# RaceDAQ_ANALOG.net
KiCad netlist of a schematic drawn in Altium Designer
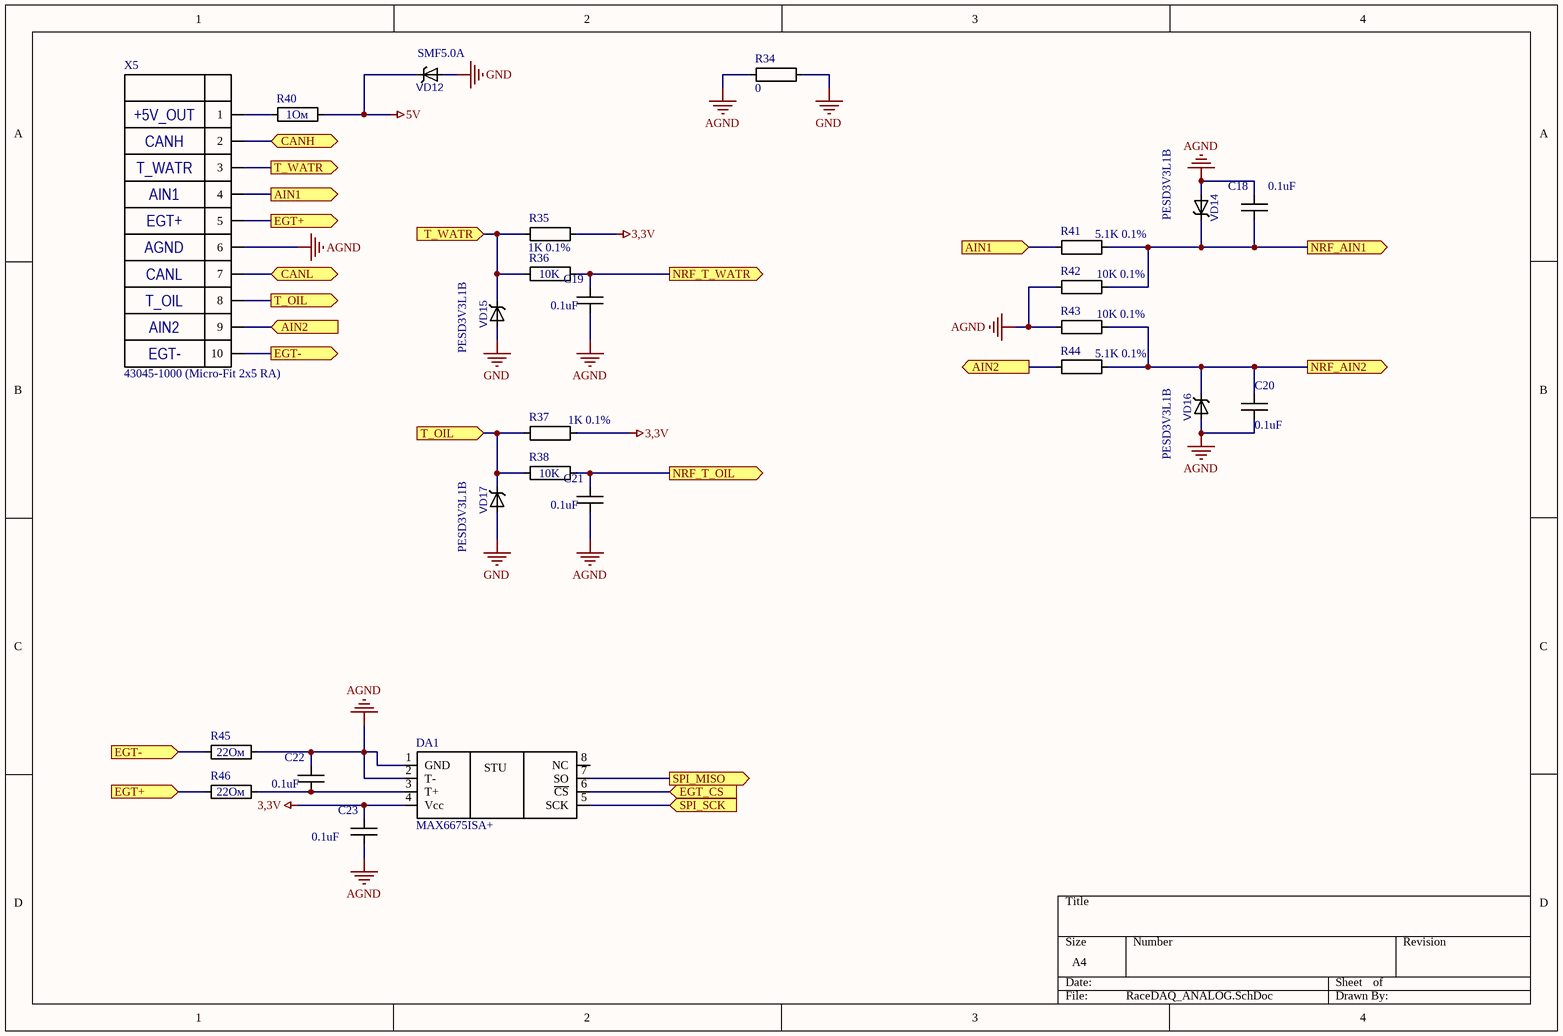
[diagram p0: RaceDAQ_ANALOG.SchDoc]

(export (version "E")
  (design (tool "Eeschema 10.0.6"))
  (components
    (comp (ref "C18")
      (value "0.1uF")
      (footprint "CAPC1608X90L25N")
      (fields (field (name "VOLTAGE") "50V") (field (name "PARTNUMBER") "CL10B104KB8NNNC"))
      (libsource (lib "tlib") (part "CAP"))
    )
    (comp (ref "C19")
      (value "0.1uF")
      (footprint "CAPC1608X90L25N")
      (fields (field (name "VOLTAGE") "50V") (field (name "PARTNUMBER") "CL10B104KB8NNNC"))
      (libsource (lib "tlib") (part "CAP"))
    )
    (comp (ref "C20")
      (value "0.1uF")
      (footprint "CAPC1608X90L25N")
      (fields (field (name "VOLTAGE") "50V") (field (name "PARTNUMBER") "CL10B104KB8NNNC"))
      (libsource (lib "tlib") (part "CAP"))
    )
    (comp (ref "C21")
      (value "0.1uF")
      (footprint "CAPC1608X90L25N")
      (fields (field (name "VOLTAGE") "50V") (field (name "PARTNUMBER") "CL10B104KB8NNNC"))
      (libsource (lib "tlib") (part "CAP"))
    )
    (comp (ref "C22")
      (value "0.1uF")
      (footprint "CAPC1608X90L25N")
      (fields (field (name "VOLTAGE") "50V") (field (name "PARTNUMBER") "CL10B104KB8NNNC"))
      (libsource (lib "tlib") (part "CAP"))
    )
    (comp (ref "C23")
      (value "0.1uF")
      (footprint "CAPC1608X90L25N")
      (fields (field (name "VOLTAGE") "50V") (field (name "PARTNUMBER") "CL10B104KB8NNNC"))
      (libsource (lib "tlib") (part "CAP"))
    )
    (comp (ref "DA1")
      (value "MAX6675ISA+")
      (footprint "SOIC127P600X175-8L87N")
      (libsource (lib "tlib") (part "MAX6675ISA+"))
    )
    (comp (ref "R34") (value "0") (footprint "RESC2012X60L35N") (libsource (lib "tlib") (part "RES")))
    (comp (ref "R35")
      (value "1K 0.1%")
      (footprint "RESC1608X55L25N")
      (fields (field (name "PARTNUMBER") "RT0603BRD071KL"))
      (libsource (lib "tlib") (part "RES"))
    )
    (comp (ref "R36") (value "10K") (footprint "RESC2012X60L35N") (libsource (lib "tlib") (part "RES")))
    (comp (ref "R37")
      (value "1K 0.1%")
      (footprint "RESC1608X55L25N")
      (fields (field (name "PARTNUMBER") "RT0603BRD071KL"))
      (libsource (lib "tlib") (part "RES"))
    )
    (comp (ref "R38") (value "10K") (footprint "RESC2012X60L35N") (libsource (lib "tlib") (part "RES")))
    (comp (ref "R40")
      (value "1Ом")
      (footprint "RESC1608X55L25N")
      (fields (field (name "PARTNUMBER") "RT0603BRD071KL"))
      (libsource (lib "tlib") (part "RES"))
    )
    (comp (ref "R41")
      (value "5.1K 0.1%")
      (footprint "RESC1608X55L25N")
      (fields (field (name "PARTNUMBER") "RT0603BRD075K1L"))
      (libsource (lib "tlib") (part "RES"))
    )
    (comp (ref "R42")
      (value "10K 0.1%")
      (footprint "RESC1608X55L25N")
      (fields (field (name "PARTNUMBER") "RT0603BRD0710KL"))
      (libsource (lib "tlib") (part "RES"))
    )
    (comp (ref "R43")
      (value "10K 0.1%")
      (footprint "RESC1608X55L25N")
      (fields (field (name "PARTNUMBER") "RT0603BRD0710KL"))
      (libsource (lib "tlib") (part "RES"))
    )
    (comp (ref "R44")
      (value "5.1K 0.1%")
      (footprint "RESC1608X55L25N")
      (fields (field (name "PARTNUMBER") "RT0603BRD075K1L"))
      (libsource (lib "tlib") (part "RES"))
    )
    (comp (ref "R45") (value "22Ом") (footprint "RESC1608X55L25N") (libsource (lib "tlib") (part "RES")))
    (comp (ref "R46") (value "22Ом") (footprint "RESC1608X55L25N") (libsource (lib "tlib") (part "RES")))
    (comp (ref "VD12") (value "SMF5.0A") (footprint "SODFL3617X110") (libsource (lib "tlib") (part "TVS_AC")))
    (comp (ref "VD14")
      (value "PESD3V3L1B")
      (footprint "SODFL1608X65N")
      (libsource (lib "tlib") (part "TVS_AC"))
    )
    (comp (ref "VD15")
      (value "PESD3V3L1B")
      (footprint "SODFL1608X65N")
      (libsource (lib "tlib") (part "TVS_AC"))
    )
    (comp (ref "VD16")
      (value "PESD3V3L1B")
      (footprint "SODFL1608X65N")
      (libsource (lib "tlib") (part "TVS_AC"))
    )
    (comp (ref "VD17")
      (value "PESD3V3L1B")
      (footprint "SODFL1608X65N")
      (libsource (lib "tlib") (part "TVS_AC"))
    )
    (comp (ref "X5")
      (value "43045-1000 (Micro-Fit 2x5 RA)")
      (footprint "43045-1000")
      (libsource (lib "tlib") (part "X10"))
    )
  )
  (nets
    (net (code "1") (name "/AIN1") (class "Default")
      (node (ref "R41") (pin "1") (pinfunction "1_1") (pintype "passive"))
      (node (ref "X5") (pin "4") (pinfunction "4_4") (pintype "passive"))
    )
    (net (code "2") (name "/AIN2") (class "Default")
      (node (ref "R44") (pin "1") (pinfunction "1_1") (pintype "passive"))
      (node (ref "X5") (pin "9") (pinfunction "9_9") (pintype "passive"))
    )
    (net (code "3") (name "/CANH") (class "Default")
      (node (ref "X5") (pin "2") (pinfunction "2_2") (pintype "passive"))
    )
    (net (code "4") (name "/CANL") (class "Default")
      (node (ref "X5") (pin "7") (pinfunction "7_7") (pintype "passive"))
    )
    (net (code "5") (name "/EGT+") (class "Default")
      (node (ref "R46") (pin "1") (pinfunction "1_1") (pintype "passive"))
      (node (ref "X5") (pin "5") (pinfunction "5_5") (pintype "passive"))
    )
    (net (code "6") (name "/EGT-") (class "Default")
      (node (ref "R45") (pin "1") (pinfunction "1_1") (pintype "passive"))
      (node (ref "X5") (pin "10") (pinfunction "10_10") (pintype "passive"))
    )
    (net (code "7") (name "/EGT_CS") (class "Default")
      (node (ref "DA1") (pin "6") (pinfunction "~{CS}_6") (pintype "passive"))
    )
    (net (code "8") (name "/NRF_AIN1") (class "Default")
      (node (ref "C18") (pin "1") (pintype "passive"))
      (node (ref "R41") (pin "2") (pinfunction "2_2") (pintype "passive"))
      (node (ref "R42") (pin "2") (pinfunction "2_2") (pintype "passive"))
      (node (ref "VD14") (pin "C") (pintype "passive"))
    )
    (net (code "9") (name "/NRF_AIN2") (class "Default")
      (node (ref "C20") (pin "2") (pintype "passive"))
      (node (ref "R43") (pin "2") (pinfunction "2_2") (pintype "passive"))
      (node (ref "R44") (pin "2") (pinfunction "2_2") (pintype "passive"))
      (node (ref "VD16") (pin "C") (pintype "passive"))
    )
    (net (code "10") (name "/NRF_T_OIL") (class "Default")
      (node (ref "C21") (pin "2") (pintype "passive"))
      (node (ref "R38") (pin "2") (pinfunction "2_2") (pintype "passive"))
    )
    (net (code "11") (name "/NRF_T_WATR") (class "Default")
      (node (ref "C19") (pin "2") (pintype "passive"))
      (node (ref "R36") (pin "2") (pinfunction "2_2") (pintype "passive"))
    )
    (net (code "12") (name "/SPI_MISO") (class "Default")
      (node (ref "DA1") (pin "7") (pinfunction "SO_7") (pintype "passive"))
    )
    (net (code "13") (name "/SPI_SCK") (class "Default")
      (node (ref "DA1") (pin "5") (pinfunction "SCK_5") (pintype "passive"))
    )
    (net (code "14") (name "/T_OIL") (class "Default")
      (node (ref "R37") (pin "1") (pinfunction "1_1") (pintype "passive"))
      (node (ref "R38") (pin "1") (pinfunction "1_1") (pintype "passive"))
      (node (ref "VD17") (pin "C") (pintype "passive"))
      (node (ref "X5") (pin "8") (pinfunction "8_8") (pintype "passive"))
    )
    (net (code "15") (name "/T_WATR") (class "Default")
      (node (ref "R35") (pin "1") (pinfunction "1_1") (pintype "passive"))
      (node (ref "R36") (pin "1") (pinfunction "1_1") (pintype "passive"))
      (node (ref "VD15") (pin "C") (pintype "passive"))
      (node (ref "X5") (pin "3") (pinfunction "3_3") (pintype "passive"))
    )
    (net (code "16") (name "3,3V") (class "Default")
      (node (ref "C23") (pin "2") (pintype "passive"))
      (node (ref "DA1") (pin "4") (pinfunction "Vcc_4") (pintype "passive"))
      (node (ref "R35") (pin "2") (pinfunction "2_2") (pintype "passive"))
      (node (ref "R37") (pin "2") (pinfunction "2_2") (pintype "passive"))
    )
    (net (code "17") (name "5V") (class "Default")
      (node (ref "R40") (pin "2") (pinfunction "2_2") (pintype "passive"))
      (node (ref "VD12") (pin "C") (pintype "passive"))
    )
    (net (code "18") (name "AGND") (class "Default")
      (node (ref "C18") (pin "2") (pintype "passive"))
      (node (ref "C19") (pin "1") (pintype "passive"))
      (node (ref "C20") (pin "1") (pintype "passive"))
      (node (ref "C21") (pin "1") (pintype "passive"))
      (node (ref "C22") (pin "2") (pintype "passive"))
      (node (ref "C23") (pin "1") (pintype "passive"))
      (node (ref "DA1") (pin "1") (pinfunction "GND_1") (pintype "passive"))
      (node (ref "DA1") (pin "2") (pinfunction "T-_2") (pintype "passive"))
      (node (ref "R34") (pin "2") (pinfunction "2_2") (pintype "passive"))
      (node (ref "R42") (pin "1") (pinfunction "1_1") (pintype "passive"))
      (node (ref "R43") (pin "1") (pinfunction "1_1") (pintype "passive"))
      (node (ref "R45") (pin "2") (pinfunction "2_2") (pintype "passive"))
      (node (ref "VD14") (pin "A") (pintype "passive"))
      (node (ref "VD16") (pin "A") (pintype "passive"))
      (node (ref "X5") (pin "6") (pinfunction "6_6") (pintype "passive"))
    )
    (net (code "19") (name "GND") (class "Default")
      (node (ref "R34") (pin "1") (pinfunction "1_1") (pintype "passive"))
      (node (ref "VD12") (pin "A") (pintype "passive"))
      (node (ref "VD15") (pin "A") (pintype "passive"))
      (node (ref "VD17") (pin "A") (pintype "passive"))
    )
    (net (code "20") (name "Net-(DA1-T+)") (class "Default")
      (node (ref "C22") (pin "1") (pintype "passive"))
      (node (ref "DA1") (pin "3") (pinfunction "T+_3") (pintype "passive"))
      (node (ref "R46") (pin "2") (pinfunction "2_2") (pintype "passive"))
    )
    (net (code "21") (name "Net-(R40-Pad1)") (class "Default")
      (node (ref "R40") (pin "1") (pinfunction "1_1") (pintype "passive"))
      (node (ref "X5") (pin "1") (pinfunction "1_1") (pintype "passive"))
    )
    (net (code "22") (name "unconnected-(DA1-NC-Pad8)") (class "Default")
      (node (ref "DA1") (pin "8") (pinfunction "NC_8") (pintype "passive"))
    )
  )
)
